# BW1098OBC_TopLevel.net
KiCad netlist of a schematic drawn in Altium Designer
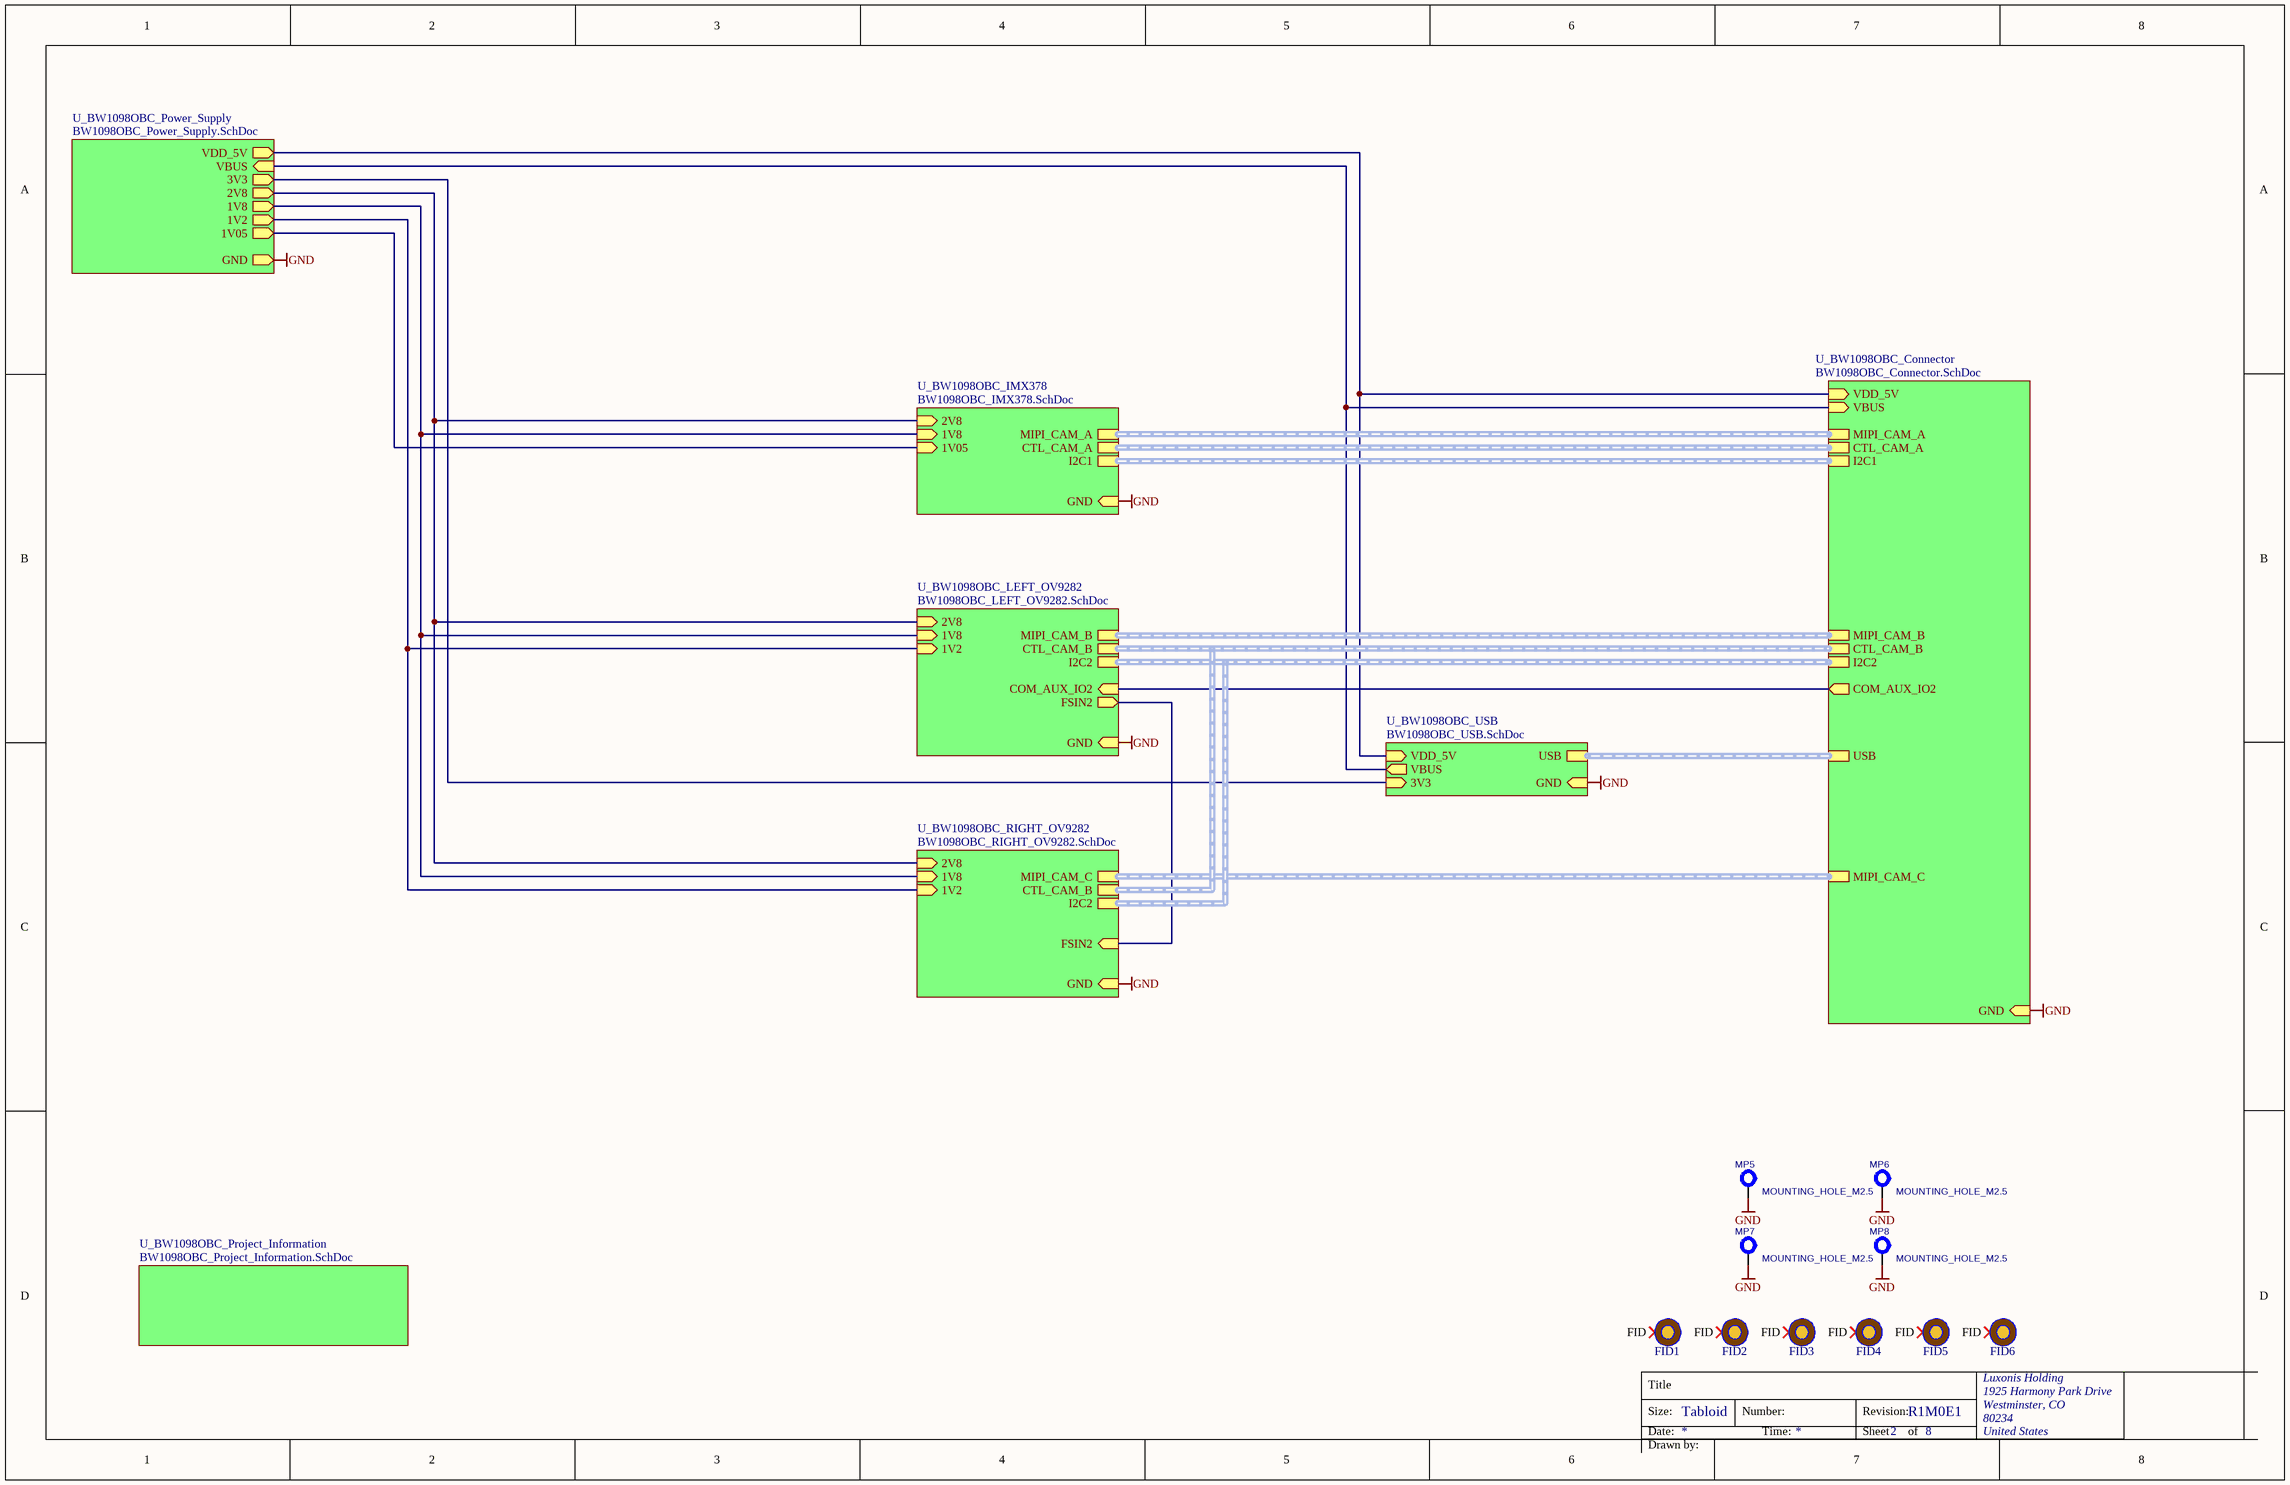
[diagram p0: BW1098OBC_TopLevel.SchDoc]

(export (version "E")
  (design (tool "Eeschema 10.0.6"))
  (components
    (comp (ref "FID1")
      (value "FIDUCIAL_ROUND_1MM")
      (footprint "LuxonisMaster:FIDUCIAL_ROUND_1MM")
      (description "Fiducial with various available footprints")
      (libsource (lib "LuxonisMaster") (part "FIDUCIAL"))
    )
    (comp (ref "FID2")
      (value "FIDUCIAL_ROUND_1MM")
      (footprint "LuxonisMaster:FIDUCIAL_ROUND_1MM")
      (description "Fiducial with various available footprints")
      (libsource (lib "LuxonisMaster") (part "FIDUCIAL"))
    )
    (comp (ref "FID3")
      (value "FIDUCIAL_ROUND_1MM")
      (footprint "LuxonisMaster:FIDUCIAL_ROUND_1MM")
      (description "Fiducial with various available footprints")
      (libsource (lib "LuxonisMaster") (part "FIDUCIAL"))
    )
    (comp (ref "FID4")
      (value "FIDUCIAL_ROUND_1MM")
      (footprint "LuxonisMaster:FIDUCIAL_ROUND_1MM")
      (description "Fiducial with various available footprints")
      (libsource (lib "LuxonisMaster") (part "FIDUCIAL"))
    )
    (comp (ref "FID5")
      (value "FIDUCIAL_ROUND_1MM")
      (footprint "LuxonisMaster:FIDUCIAL_ROUND_1MM")
      (description "Fiducial with various available footprints")
      (libsource (lib "LuxonisMaster") (part "FIDUCIAL"))
    )
    (comp (ref "FID6")
      (value "FIDUCIAL_ROUND_1MM")
      (footprint "LuxonisMaster:FIDUCIAL_ROUND_1MM")
      (description "Fiducial with various available footprints")
      (libsource (lib "LuxonisMaster") (part "FIDUCIAL"))
    )
    (comp (ref "MP5")
      (value "MOUNTING_HOLE_M2.5")
      (footprint "LuxonisMaster:MOUNTING_HOLE_M2.5")
      (description "=CurrentFootprint")
      (libsource (lib "LuxonisMaster") (part "MP_Mounting-Holes"))
    )
    (comp (ref "MP6")
      (value "MOUNTING_HOLE_M2.5")
      (footprint "LuxonisMaster:MOUNTING_HOLE_M2.5")
      (description "=CurrentFootprint")
      (libsource (lib "LuxonisMaster") (part "MP_Mounting-Holes"))
    )
    (comp (ref "MP7")
      (value "MOUNTING_HOLE_M2.5")
      (footprint "LuxonisMaster:MOUNTING_HOLE_M2.5")
      (description "=CurrentFootprint")
      (libsource (lib "LuxonisMaster") (part "MP_Mounting-Holes"))
    )
    (comp (ref "MP8")
      (value "MOUNTING_HOLE_M2.5")
      (footprint "LuxonisMaster:MOUNTING_HOLE_M2.5")
      (description "=CurrentFootprint")
      (libsource (lib "LuxonisMaster") (part "MP_Mounting-Holes"))
    )
  )
  (nets
    (net (code "18") (name "GND") (class "Default")
      (node (ref "MP5") (pin "1") (pintype "passive"))
      (node (ref "MP6") (pin "1") (pintype "passive"))
      (node (ref "MP7") (pin "1") (pintype "passive"))
      (node (ref "MP8") (pin "1") (pintype "passive"))
    )
    (net (code "19") (name "unconnected-(FID1-PadFID)") (class "Default")
      (node (ref "FID1") (pin "FID") (pinfunction "FID_FID") (pintype "input+no_connect"))
    )
    (net (code "20") (name "unconnected-(FID2-PadFID)") (class "Default")
      (node (ref "FID2") (pin "FID") (pinfunction "FID_FID") (pintype "input+no_connect"))
    )
    (net (code "21") (name "unconnected-(FID3-PadFID)") (class "Default")
      (node (ref "FID3") (pin "FID") (pinfunction "FID_FID") (pintype "input+no_connect"))
    )
    (net (code "22") (name "unconnected-(FID4-PadFID)") (class "Default")
      (node (ref "FID4") (pin "FID") (pinfunction "FID_FID") (pintype "input+no_connect"))
    )
    (net (code "23") (name "unconnected-(FID5-PadFID)") (class "Default")
      (node (ref "FID5") (pin "FID") (pinfunction "FID_FID") (pintype "input+no_connect"))
    )
    (net (code "24") (name "unconnected-(FID6-PadFID)") (class "Default")
      (node (ref "FID6") (pin "FID") (pinfunction "FID_FID") (pintype "input+no_connect"))
    )
  )
)
